# sensor.net
KiCad netlist of a schematic drawn in Altium Designer
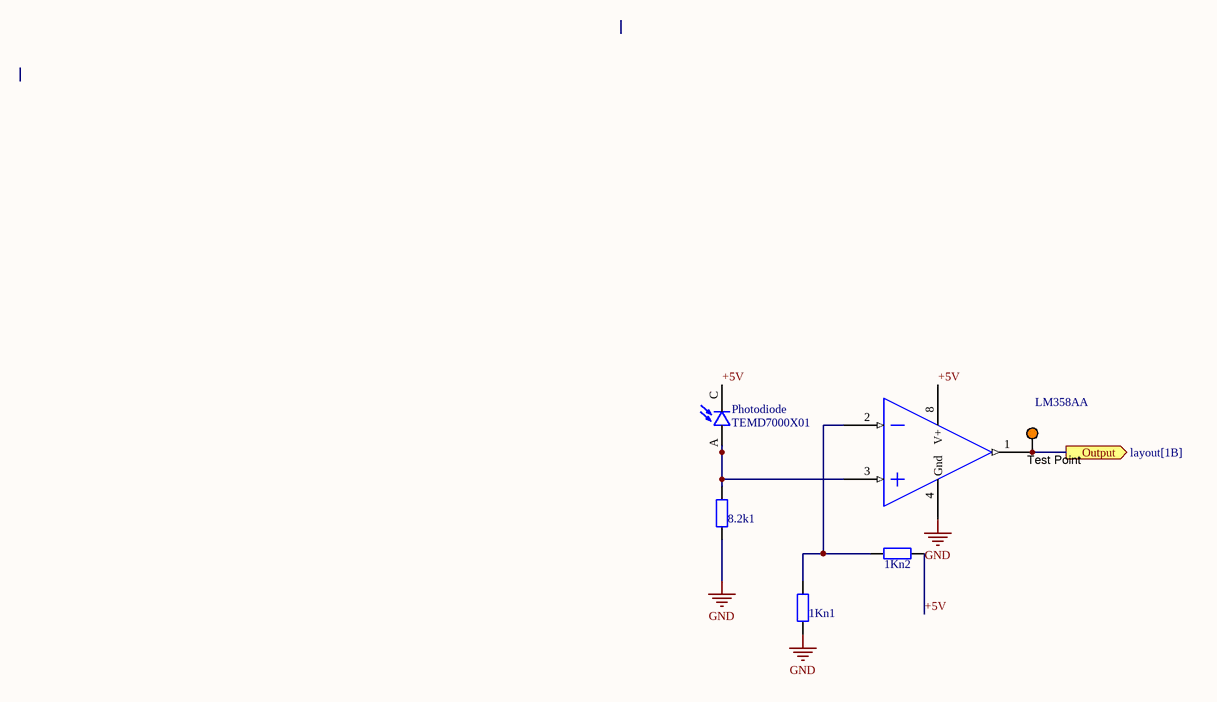
[diagram p0: sensor.SchDoc]

(export (version "E")
  (design (tool "Eeschema 10.0.6"))
  (components
    (comp (ref "1Kn1")
      (value "1K")
      (footprint "ECE-RESA0.4TH")
      (description "RES MF 1K0 TH")
      (libsource (lib "") (part "Resistor_1"))
    )
    (comp (ref "1Kn2")
      (value "1K")
      (footprint "ECE-RESA0.4TH")
      (description "RES MF 1K0 TH")
      (libsource (lib "EceParts") (part "Resistor"))
    )
    (comp (ref "8.2k1")
      (value "8K2")
      (footprint "ECE-RESA0.4TH")
      (description "RES MF 8K2 TH")
      (libsource (lib "") (part "Resistor_1"))
    )
    (comp (ref "LM358A")
      (value "LM358")
      (footprint "ECE-DIP8TH")
      (description "IC OPAMP LM358 DUAL TH")
      (libsource (lib "EceParts") (part "LM358"))
    )
    (comp (ref "Photodiode")
      (value "TEMD7000X01")
      (footprint "XDCR_TEMD7000X01")
      (description "Photodiode 900nm 100ns 120Â° 0805 (2012 Metric)")
      (fields (field (name "MF") "Vishay Semiconductor"))
      (libsource (lib "TEMD7000X01") (part "TEMD7000X01"))
    )
    (comp (ref "Test Point")
      (value "5003")
      (footprint "TP_TH")
      (description "Test Point, Orange, 1-Pin THD, RoHS")
      (libsource (lib "EE209_Library") (part "TestPoint"))
    )
  )
  (nets
    (net (code "1") (name "/+5V") (class "Default")
      (node (ref "1Kn2") (pin "2") (pinfunction "2_2") (pintype "passive"))
      (node (ref "LM358A") (pin "8") (pinfunction "V+_8") (pintype "power_in"))
      (node (ref "Photodiode") (pin "C") (pinfunction "C_C") (pintype "passive"))
    )
    (net (code "2") (name "/Output") (class "Default")
      (node (ref "LM358A") (pin "1") (pinfunction "OUT1_1") (pintype "output"))
      (node (ref "Test Point") (pin "1") (pinfunction "1_1") (pintype "passive"))
    )
    (net (code "3") (name "GND") (class "Default")
      (node (ref "1Kn1") (pin "1") (pinfunction "1_1") (pintype "passive"))
      (node (ref "8.2k1") (pin "1") (pinfunction "1_1") (pintype "passive"))
      (node (ref "LM358A") (pin "4") (pinfunction "Gnd_4") (pintype "power_in"))
    )
    (net (code "4") (name "Net-(LM358AA-IN1(+))") (class "Default")
      (node (ref "8.2k1") (pin "2") (pinfunction "2_2") (pintype "passive"))
      (node (ref "LM358A") (pin "3") (pinfunction "IN1(+)_3") (pintype "input"))
      (node (ref "Photodiode") (pin "A") (pinfunction "A_A") (pintype "passive"))
    )
    (net (code "5") (name "Net-(LM358AA-IN1(-))") (class "Default")
      (node (ref "1Kn1") (pin "2") (pinfunction "2_2") (pintype "passive"))
      (node (ref "1Kn2") (pin "1") (pinfunction "1_1") (pintype "passive"))
      (node (ref "LM358A") (pin "2") (pinfunction "IN1(-)_2") (pintype "input"))
    )
  )
)
